# ProPrj_X-Link_V9_3_M_2024-11-03.net
KiCad netlist of a schematic drawn in EasyEDA Pro
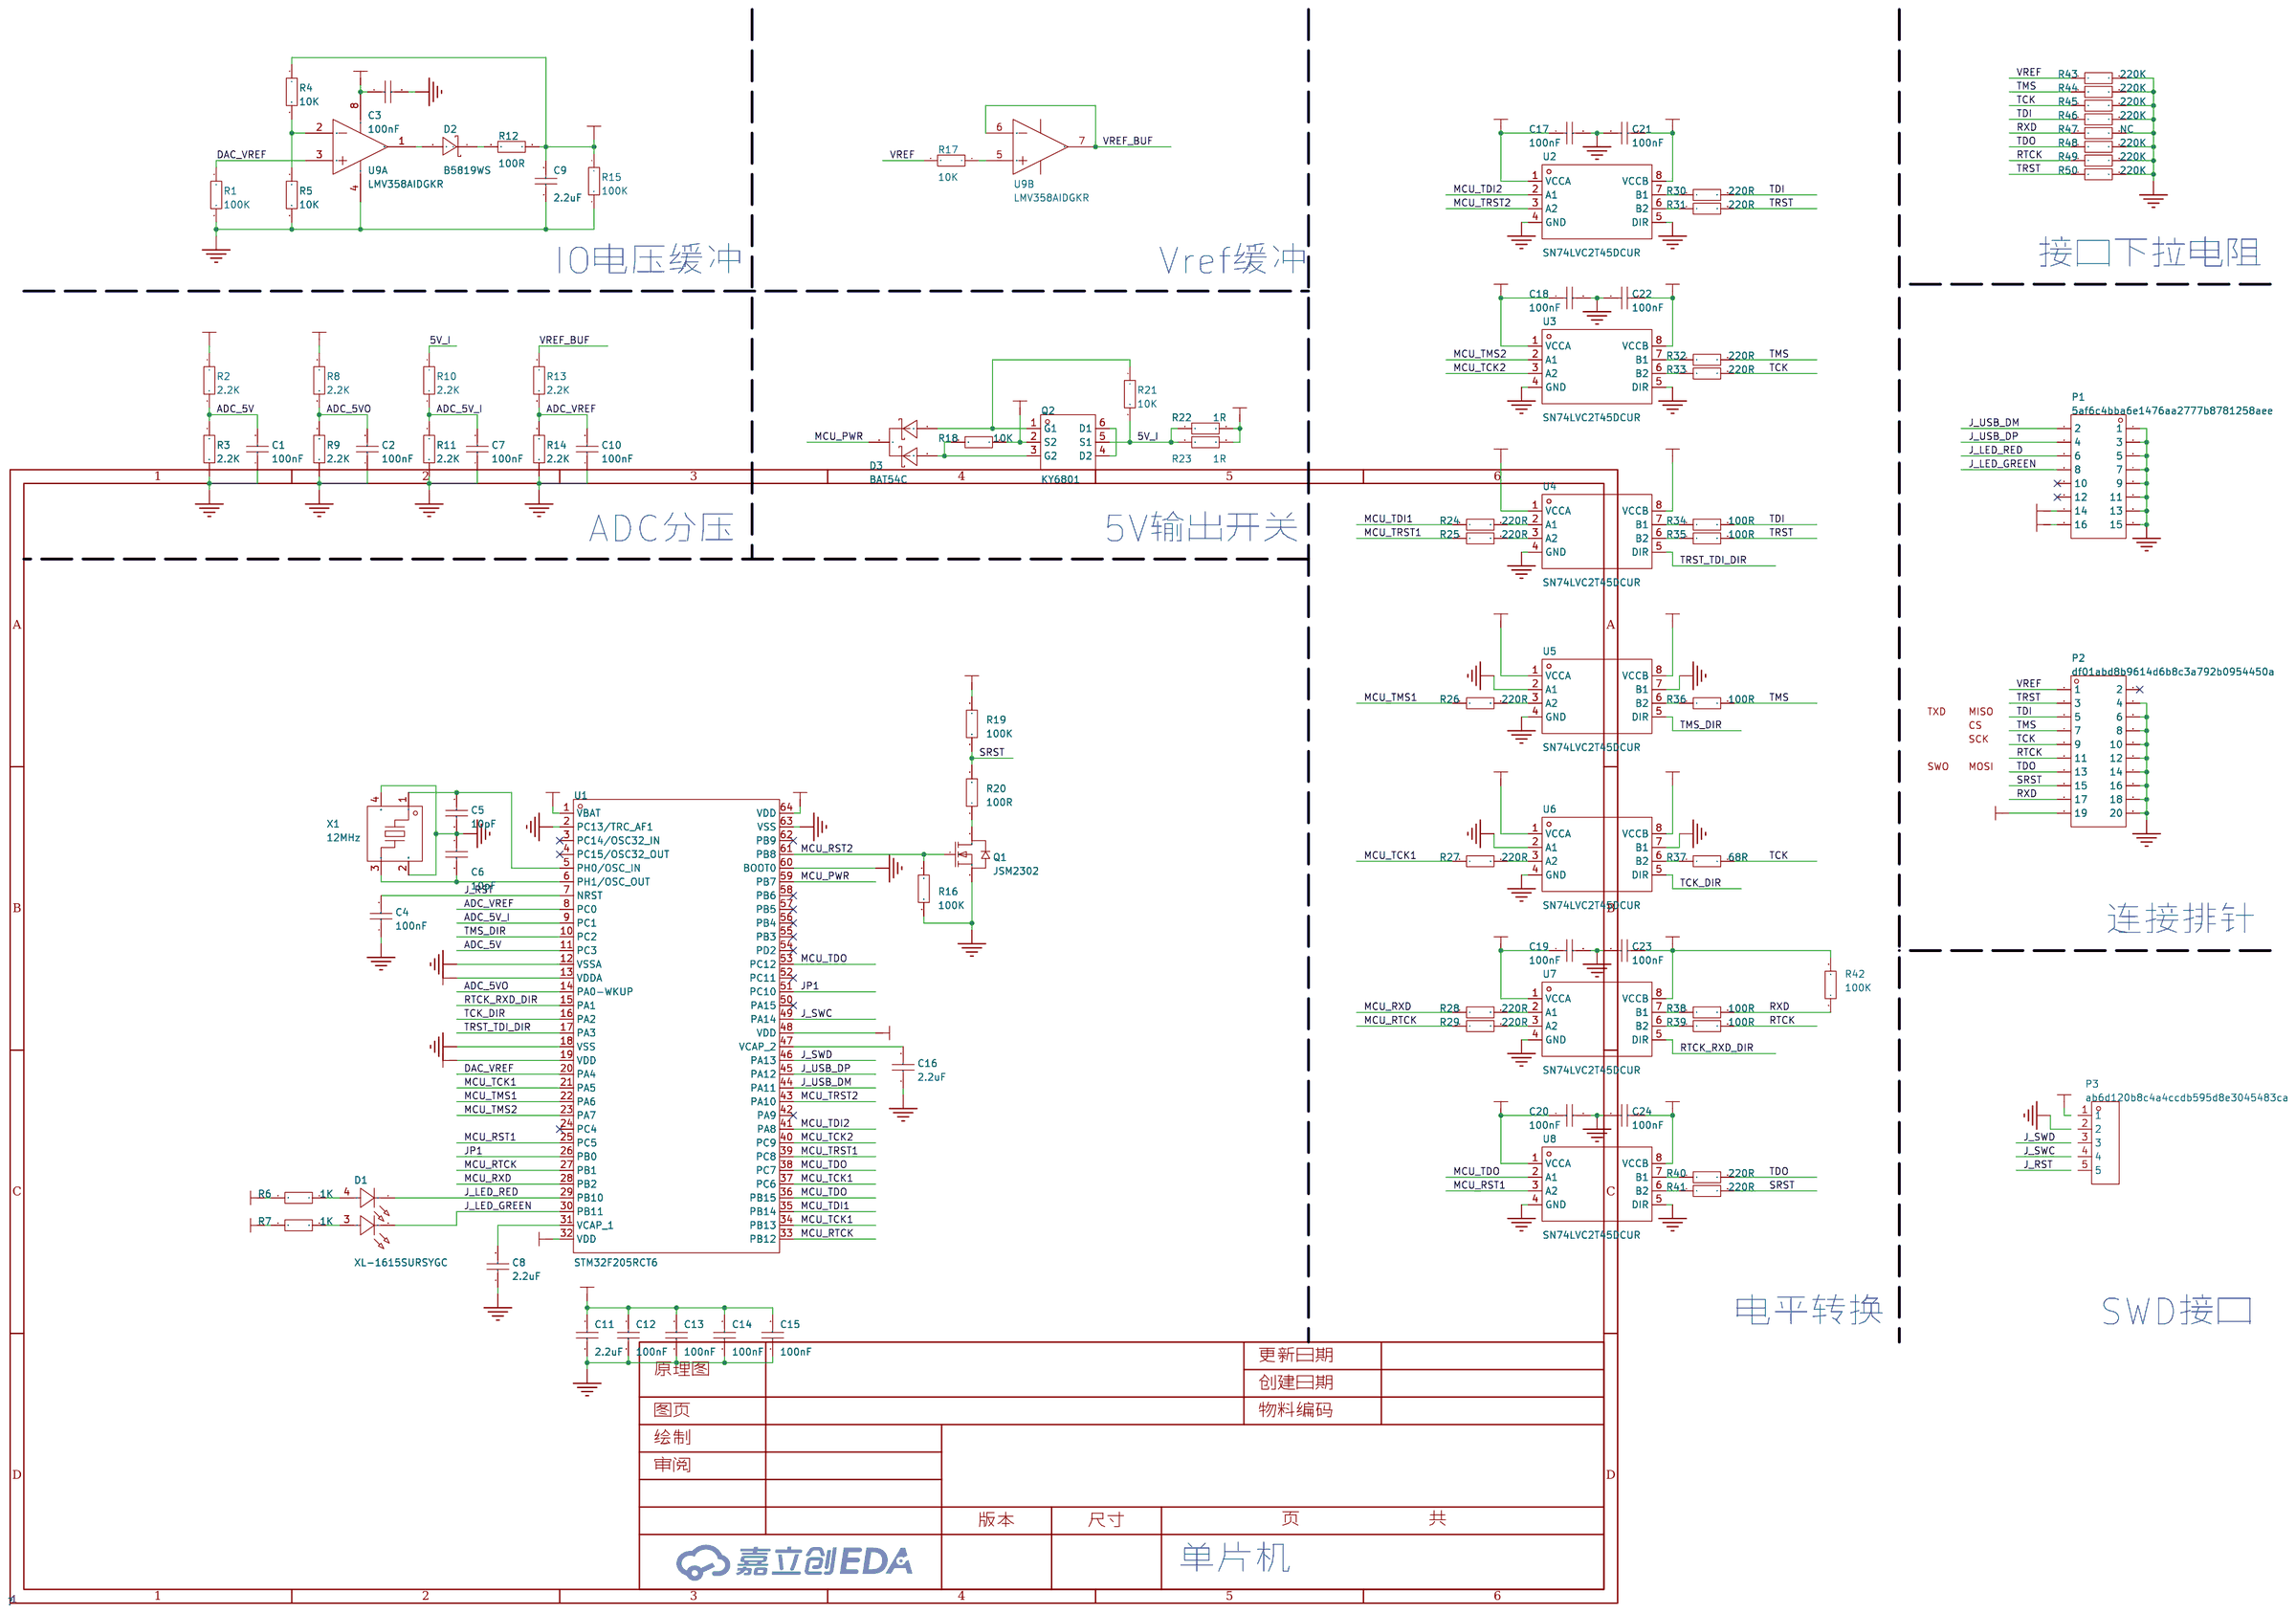
[diagram p0: schematic sheet]

(export (version "E")
  (design (tool "Eeschema 10.0.6"))
  (components
    (comp (ref "C1")
      (value "100nF")
      (footprint "easyedapro:C0402")
      (libsource (lib "easyedapro") (part "C0402"))
    )
    (comp (ref "C2")
      (value "100nF")
      (footprint "easyedapro:C0402")
      (libsource (lib "easyedapro") (part "C0402"))
    )
    (comp (ref "C3")
      (value "100nF")
      (footprint "easyedapro:C0402")
      (libsource (lib "easyedapro") (part "C0402"))
    )
    (comp (ref "C4")
      (value "100nF")
      (footprint "easyedapro:C0603")
      (libsource (lib "easyedapro") (part "C0603"))
    )
    (comp (ref "C5")
      (value "10pF")
      (footprint "easyedapro:C0402")
      (libsource (lib "easyedapro") (part "C0402"))
    )
    (comp (ref "C6")
      (value "10pF")
      (footprint "easyedapro:C0402")
      (libsource (lib "easyedapro") (part "C0402"))
    )
    (comp (ref "C7")
      (value "100nF")
      (footprint "easyedapro:C0402")
      (libsource (lib "easyedapro") (part "C0402"))
    )
    (comp (ref "C8")
      (value "2.2uF")
      (footprint "easyedapro:C0603")
      (libsource (lib "easyedapro") (part "C0603"))
    )
    (comp (ref "C9")
      (value "2.2uF")
      (footprint "easyedapro:C0402")
      (libsource (lib "easyedapro") (part "C0402"))
    )
    (comp (ref "C10")
      (value "100nF")
      (footprint "easyedapro:C0402")
      (libsource (lib "easyedapro") (part "C0402"))
    )
    (comp (ref "C11")
      (value "2.2uF")
      (footprint "easyedapro:C0603")
      (libsource (lib "easyedapro") (part "C0603"))
    )
    (comp (ref "C12")
      (value "100nF")
      (footprint "easyedapro:C0603")
      (libsource (lib "easyedapro") (part "C0603"))
    )
    (comp (ref "C13")
      (value "100nF")
      (footprint "easyedapro:C0603")
      (libsource (lib "easyedapro") (part "C0603"))
    )
    (comp (ref "C14")
      (value "100nF")
      (footprint "easyedapro:C0603")
      (libsource (lib "easyedapro") (part "C0603"))
    )
    (comp (ref "C15")
      (value "100nF")
      (footprint "easyedapro:C0603")
      (libsource (lib "easyedapro") (part "C0603"))
    )
    (comp (ref "C16")
      (value "2.2uF")
      (footprint "easyedapro:C0603")
      (libsource (lib "easyedapro") (part "C0603"))
    )
    (comp (ref "C17")
      (value "100nF")
      (footprint "easyedapro:C0603")
      (libsource (lib "easyedapro") (part "C0603"))
    )
    (comp (ref "C18")
      (value "100nF")
      (footprint "easyedapro:C0603")
      (libsource (lib "easyedapro") (part "C0603"))
    )
    (comp (ref "C19")
      (value "100nF")
      (footprint "easyedapro:C0603")
      (libsource (lib "easyedapro") (part "C0603"))
    )
    (comp (ref "C20")
      (value "100nF")
      (footprint "easyedapro:C0603")
      (libsource (lib "easyedapro") (part "C0603"))
    )
    (comp (ref "C21")
      (value "100nF")
      (footprint "easyedapro:C0603")
      (libsource (lib "easyedapro") (part "C0603"))
    )
    (comp (ref "C22")
      (value "100nF")
      (footprint "easyedapro:C0603")
      (libsource (lib "easyedapro") (part "C0603"))
    )
    (comp (ref "C23")
      (value "100nF")
      (footprint "easyedapro:C0603")
      (libsource (lib "easyedapro") (part "C0603"))
    )
    (comp (ref "C24")
      (value "100nF")
      (footprint "easyedapro:C0603")
      (libsource (lib "easyedapro") (part "C0603"))
    )
    (comp (ref "D1")
      (value "XL-1615SURSYGC")
      (footprint "easyedapro:LED1615")
      (fields (field (name "Manufacturer") "XINGLIGHT(成兴光)"))
      (libsource (lib "easyedapro") (part "LED1615"))
    )
    (comp (ref "D2")
      (value "B5819WS")
      (footprint "easyedapro:SOD-323_L1.8-W1.3-LS2.5-RD")
      (description "正向压降(Vf):600mV@1A;直流反向耐压(Vr):40V;平均整流电流(Io):1A;")
      (fields (field (name "Manufacturer") "CJ(江苏长电/长晶)"))
      (libsource (lib "easyedapro") (part "B5819WS_C22624"))
    )
    (comp (ref "D3")
      (value "BAT54C")
      (footprint "easyedapro:SOT-23-3_L2.9-W1.3-P1.90-LS2.4-BR")
      (description "二极管配置:1对共阴极;正向压降(Vf):1V@100mA;直流反向耐压(Vr):30V;平均整流电流(Io):100mA;")
      (fields (field (name "Manufacturer") "JSMSEMI(杰盛微)"))
      (libsource (lib "easyedapro") (part "BAR43CFILM"))
    )
    (comp (ref "P1")
      (value "5af6c4bba6e1476aa2777b8781258aee")
      (footprint "easyedapro:HDR-TH_16P-P1.27-V-M-R2-C8-S1.27-1")
      (libsource (lib "easyedapro") (part "HDR2x8_1.27"))
    )
    (comp (ref "P2")
      (value "df01abd8b9614d6b8c3a792b0954450a")
      (footprint "easyedapro:HDR-TH_20P-P1.27-V-M-R2-C10-S1.27")
      (libsource (lib "easyedapro") (part "HDR2x10_1.27"))
    )
    (comp (ref "P3")
      (value "ab6d120b8c4a4ccdb595d8e3045483ca")
      (footprint "easyedapro:HDR-TH_5P-P1.27-V-M")
      (libsource (lib "easyedapro") (part "HDR1x5_1.27"))
    )
    (comp (ref "Q1")
      (value "JSM2302")
      (footprint "easyedapro:SOT-23-3_L2.9-W1.3-P1.90-LS2.4-BR")
      (fields (field (name "Manufacturer") "JSMSEMI(杰盛微)"))
      (libsource (lib "easyedapro") (part "SI2302A"))
    )
    (comp (ref "Q2")
      (value "KY6801")
      (footprint "easyedapro:SOT-23-6_L2.9-W1.6-P0.95-LS2.8-BR")
      (description "类型:-;漏源电压(Vdss):-;连续漏极电流(Id):-;功率(Pd):-;导通电阻(RDS(on)@Vgs,Id):-;阈值电压(Vgs(th)@Id):-;")
      (fields (field (name "Manufacturer") "KY(韩景元)"))
      (libsource (lib "easyedapro") (part "FDC6312P_C241767"))
    )
    (comp (ref "R1")
      (value "100K")
      (footprint "easyedapro:R0402")
      (libsource (lib "easyedapro") (part "R0402"))
    )
    (comp (ref "R2")
      (value "2.2K")
      (footprint "easyedapro:R0402")
      (libsource (lib "easyedapro") (part "R0402"))
    )
    (comp (ref "R3")
      (value "2.2K")
      (footprint "easyedapro:R0402")
      (libsource (lib "easyedapro") (part "R0402"))
    )
    (comp (ref "R4")
      (value "10K")
      (footprint "easyedapro:R0402")
      (libsource (lib "easyedapro") (part "R0402"))
    )
    (comp (ref "R5")
      (value "10K")
      (footprint "easyedapro:R0402")
      (libsource (lib "easyedapro") (part "R0402"))
    )
    (comp (ref "R6") (value "1K") (footprint "easyedapro:R0603") (libsource (lib "easyedapro") (part "电阻")))
    (comp (ref "R7") (value "1K") (footprint "easyedapro:R0603") (libsource (lib "easyedapro") (part "电阻")))
    (comp (ref "R8")
      (value "2.2K")
      (footprint "easyedapro:R0402")
      (libsource (lib "easyedapro") (part "R0402"))
    )
    (comp (ref "R9")
      (value "2.2K")
      (footprint "easyedapro:R0402")
      (libsource (lib "easyedapro") (part "R0402"))
    )
    (comp (ref "R10")
      (value "2.2K")
      (footprint "easyedapro:R0402")
      (libsource (lib "easyedapro") (part "R0402"))
    )
    (comp (ref "R11")
      (value "2.2K")
      (footprint "easyedapro:R0402")
      (libsource (lib "easyedapro") (part "R0402"))
    )
    (comp (ref "R12")
      (value "100R")
      (footprint "easyedapro:R0402")
      (libsource (lib "easyedapro") (part "R0402"))
    )
    (comp (ref "R13")
      (value "2.2K")
      (footprint "easyedapro:R0402")
      (libsource (lib "easyedapro") (part "R0402"))
    )
    (comp (ref "R14")
      (value "2.2K")
      (footprint "easyedapro:R0402")
      (libsource (lib "easyedapro") (part "R0402"))
    )
    (comp (ref "R15")
      (value "100K")
      (footprint "easyedapro:R0402")
      (libsource (lib "easyedapro") (part "R0402"))
    )
    (comp (ref "R16")
      (value "100K")
      (footprint "easyedapro:R0603")
      (libsource (lib "easyedapro") (part "电阻"))
    )
    (comp (ref "R17")
      (value "10K")
      (footprint "easyedapro:R0402")
      (libsource (lib "easyedapro") (part "R0402"))
    )
    (comp (ref "R18") (value "10K") (footprint "easyedapro:R0603") (libsource (lib "easyedapro") (part "电阻")))
    (comp (ref "R19")
      (value "100K")
      (footprint "easyedapro:R0603")
      (libsource (lib "easyedapro") (part "电阻"))
    )
    (comp (ref "R20")
      (value "100R")
      (footprint "easyedapro:R0603")
      (libsource (lib "easyedapro") (part "电阻"))
    )
    (comp (ref "R21") (value "10K") (footprint "easyedapro:R0603") (libsource (lib "easyedapro") (part "电阻")))
    (comp (ref "R22")
      (value "1R")
      (footprint "easyedapro:R0805")
      (libsource (lib "easyedapro") (part "R0805"))
    )
    (comp (ref "R23")
      (value "1R")
      (footprint "easyedapro:R0805")
      (libsource (lib "easyedapro") (part "R0805"))
    )
    (comp (ref "R24")
      (value "220R")
      (footprint "easyedapro:R0603")
      (libsource (lib "easyedapro") (part "电阻"))
    )
    (comp (ref "R25")
      (value "220R")
      (footprint "easyedapro:R0603")
      (libsource (lib "easyedapro") (part "电阻"))
    )
    (comp (ref "R26")
      (value "220R")
      (footprint "easyedapro:R0603")
      (libsource (lib "easyedapro") (part "电阻"))
    )
    (comp (ref "R27")
      (value "220R")
      (footprint "easyedapro:R0603")
      (libsource (lib "easyedapro") (part "电阻"))
    )
    (comp (ref "R28")
      (value "220R")
      (footprint "easyedapro:R0603")
      (libsource (lib "easyedapro") (part "电阻"))
    )
    (comp (ref "R29")
      (value "220R")
      (footprint "easyedapro:R0603")
      (libsource (lib "easyedapro") (part "电阻"))
    )
    (comp (ref "R30")
      (value "220R")
      (footprint "easyedapro:R0603")
      (libsource (lib "easyedapro") (part "电阻"))
    )
    (comp (ref "R31")
      (value "220R")
      (footprint "easyedapro:R0603")
      (libsource (lib "easyedapro") (part "电阻"))
    )
    (comp (ref "R32")
      (value "220R")
      (footprint "easyedapro:R0603")
      (libsource (lib "easyedapro") (part "电阻"))
    )
    (comp (ref "R33")
      (value "220R")
      (footprint "easyedapro:R0603")
      (libsource (lib "easyedapro") (part "电阻"))
    )
    (comp (ref "R34")
      (value "100R")
      (footprint "easyedapro:R0603")
      (libsource (lib "easyedapro") (part "电阻"))
    )
    (comp (ref "R35")
      (value "100R")
      (footprint "easyedapro:R0603")
      (libsource (lib "easyedapro") (part "电阻"))
    )
    (comp (ref "R36")
      (value "100R")
      (footprint "easyedapro:R0603")
      (libsource (lib "easyedapro") (part "电阻"))
    )
    (comp (ref "R37") (value "68R") (footprint "easyedapro:R0603") (libsource (lib "easyedapro") (part "电阻")))
    (comp (ref "R38")
      (value "100R")
      (footprint "easyedapro:R0603")
      (libsource (lib "easyedapro") (part "电阻"))
    )
    (comp (ref "R39")
      (value "100R")
      (footprint "easyedapro:R0603")
      (libsource (lib "easyedapro") (part "电阻"))
    )
    (comp (ref "R40")
      (value "220R")
      (footprint "easyedapro:R0603")
      (libsource (lib "easyedapro") (part "电阻"))
    )
    (comp (ref "R41")
      (value "220R")
      (footprint "easyedapro:R0603")
      (libsource (lib "easyedapro") (part "电阻"))
    )
    (comp (ref "R42")
      (value "100K")
      (footprint "easyedapro:R0603")
      (libsource (lib "easyedapro") (part "电阻"))
    )
    (comp (ref "R43")
      (value "220K")
      (footprint "easyedapro:R0603")
      (libsource (lib "easyedapro") (part "电阻"))
    )
    (comp (ref "R44")
      (value "220K")
      (footprint "easyedapro:R0603")
      (libsource (lib "easyedapro") (part "电阻"))
    )
    (comp (ref "R45")
      (value "220K")
      (footprint "easyedapro:R0603")
      (libsource (lib "easyedapro") (part "电阻"))
    )
    (comp (ref "R46")
      (value "220K")
      (footprint "easyedapro:R0603")
      (libsource (lib "easyedapro") (part "电阻"))
    )
    (comp (ref "R47") (value "NC") (footprint "easyedapro:R0603") (libsource (lib "easyedapro") (part "电阻")))
    (comp (ref "R48")
      (value "220K")
      (footprint "easyedapro:R0603")
      (libsource (lib "easyedapro") (part "电阻"))
    )
    (comp (ref "R49")
      (value "220K")
      (footprint "easyedapro:R0603")
      (libsource (lib "easyedapro") (part "电阻"))
    )
    (comp (ref "R50")
      (value "220K")
      (footprint "easyedapro:R0603")
      (libsource (lib "easyedapro") (part "电阻"))
    )
    (comp (ref "U1")
      (value "STM32F205RCT6")
      (footprint "easyedapro:LQFP-64_L10.0-W10.0-P0.50-LS12.0-BL")
      (description "CPU内核:CM3;程序存储容量:256KB;GPIO端口数量:51;工作电压范围:1.8V~3.6V;CPU最大主频:120MHz;")
      (fields (field (name "Manufacturer") "ST(意法半导体)"))
      (libsource (lib "easyedapro") (part "STM32F205RCT6"))
    )
    (comp (ref "U2")
      (value "SN74LVC2T45DCUR")
      (footprint "easyedapro:VSSOP-8_L2.4-W2.1-P0.50-LS3.2-BR")
      (description "SN74LVC2T45 具有可配置电压转换和三态输出的 2 位双电源总线收发器")
      (fields (field (name "Manufacturer") "TI(德州仪器)"))
      (libsource (lib "easyedapro") (part "SN74LVC2T45DCUR"))
    )
    (comp (ref "U3")
      (value "SN74LVC2T45DCUR")
      (footprint "easyedapro:VSSOP-8_L2.4-W2.1-P0.50-LS3.2-BR")
      (description "SN74LVC2T45 具有可配置电压转换和三态输出的 2 位双电源总线收发器")
      (fields (field (name "Manufacturer") "TI(德州仪器)"))
      (libsource (lib "easyedapro") (part "SN74LVC2T45DCUR"))
    )
    (comp (ref "U4")
      (value "SN74LVC2T45DCUR")
      (footprint "easyedapro:VSSOP-8_L2.4-W2.1-P0.50-LS3.2-BR")
      (description "SN74LVC2T45 具有可配置电压转换和三态输出的 2 位双电源总线收发器")
      (fields (field (name "Manufacturer") "TI(德州仪器)"))
      (libsource (lib "easyedapro") (part "SN74LVC2T45DCUR"))
    )
    (comp (ref "U5")
      (value "SN74LVC2T45DCUR")
      (footprint "easyedapro:VSSOP-8_L2.4-W2.1-P0.50-LS3.2-BR")
      (description "SN74LVC2T45 具有可配置电压转换和三态输出的 2 位双电源总线收发器")
      (fields (field (name "Manufacturer") "TI(德州仪器)"))
      (libsource (lib "easyedapro") (part "SN74LVC2T45DCUR"))
    )
    (comp (ref "U6")
      (value "SN74LVC2T45DCUR")
      (footprint "easyedapro:VSSOP-8_L2.4-W2.1-P0.50-LS3.2-BR")
      (description "SN74LVC2T45 具有可配置电压转换和三态输出的 2 位双电源总线收发器")
      (fields (field (name "Manufacturer") "TI(德州仪器)"))
      (libsource (lib "easyedapro") (part "SN74LVC2T45DCUR"))
    )
    (comp (ref "U7")
      (value "SN74LVC2T45DCUR")
      (footprint "easyedapro:VSSOP-8_L2.4-W2.1-P0.50-LS3.2-BR")
      (description "SN74LVC2T45 具有可配置电压转换和三态输出的 2 位双电源总线收发器")
      (fields (field (name "Manufacturer") "TI(德州仪器)"))
      (libsource (lib "easyedapro") (part "SN74LVC2T45DCUR"))
    )
    (comp (ref "U8")
      (value "SN74LVC2T45DCUR")
      (footprint "easyedapro:VSSOP-8_L2.4-W2.1-P0.50-LS3.2-BR")
      (description "SN74LVC2T45 具有可配置电压转换和三态输出的 2 位双电源总线收发器")
      (fields (field (name "Manufacturer") "TI(德州仪器)"))
      (libsource (lib "easyedapro") (part "SN74LVC2T45DCUR"))
    )
    (comp (ref "U9")
      (value "LMV358AIDGKR")
      (footprint "easyedapro:VSSOP-8_L3.0-W3.0-P0.65-LS5.0-BL")
      (description "放大器数:双路;增益带宽积(GBP):1MHz;输入偏置电流(Ib):10pA;压摆率(SR):1.7V/us;带宽(-3db):-;轨到轨:-;")
      (fields (field (name "Manufacturer") "TI(德州仪器)"))
      (libsource (lib "easyedapro") (part "LMV358AIDGKR"))
    )
    (comp (ref "X1")
      (value "12MHz")
      (footprint "easyedapro:CRYSTAL-SMD_4P-L3.2-W2.5-BL-A")
      (libsource (lib "easyedapro") (part "XTAL3225"))
    )
  )
  (nets
    (net (code "1") (name "/5V_I") (class "Default")
      (node (ref "Q2") (pin "5") (pinfunction "S1_5") (pintype "unspecified"))
      (node (ref "R10") (pin "1") (pinfunction "1_1") (pintype "input"))
      (node (ref "R21") (pin "2") (pinfunction "2_2") (pintype "input"))
      (node (ref "R22") (pin "1") (pinfunction "1_1") (pintype "input"))
      (node (ref "R23") (pin "1") (pinfunction "1_1") (pintype "input"))
    )
    (net (code "2") (name "/ADC_5V") (class "Default")
      (node (ref "C1") (pin "2") (pinfunction "2_2") (pintype "input"))
      (node (ref "R2") (pin "2") (pinfunction "2_2") (pintype "input"))
      (node (ref "R3") (pin "1") (pinfunction "1_1") (pintype "input"))
      (node (ref "U1") (pin "11") (pinfunction "PC3_11") (pintype "unspecified"))
    )
    (net (code "3") (name "/ADC_5VO") (class "Default")
      (node (ref "C2") (pin "2") (pinfunction "2_2") (pintype "input"))
      (node (ref "R8") (pin "2") (pinfunction "2_2") (pintype "input"))
      (node (ref "R9") (pin "1") (pinfunction "1_1") (pintype "input"))
      (node (ref "U1") (pin "14") (pinfunction "PA0-WKUP_14") (pintype "unspecified"))
    )
    (net (code "4") (name "/ADC_5V_I") (class "Default")
      (node (ref "C7") (pin "2") (pinfunction "2_2") (pintype "input"))
      (node (ref "R10") (pin "2") (pinfunction "2_2") (pintype "input"))
      (node (ref "R11") (pin "1") (pinfunction "1_1") (pintype "input"))
      (node (ref "U1") (pin "9") (pinfunction "PC1_9") (pintype "unspecified"))
    )
    (net (code "5") (name "/ADC_VREF") (class "Default")
      (node (ref "C10") (pin "2") (pinfunction "2_2") (pintype "input"))
      (node (ref "R13") (pin "2") (pinfunction "2_2") (pintype "input"))
      (node (ref "R14") (pin "1") (pinfunction "1_1") (pintype "input"))
      (node (ref "U1") (pin "8") (pinfunction "PC0_8") (pintype "unspecified"))
    )
    (net (code "6") (name "/DAC_VREF") (class "Default")
      (node (ref "R1") (pin "1") (pinfunction "1_1") (pintype "input"))
      (node (ref "U1") (pin "20") (pinfunction "PA4_20") (pintype "unspecified"))
      (node (ref "U9") (pin "3") (pinfunction "+INA_3") (pintype "unspecified"))
    )
    (net (code "7") (name "/JP1") (class "Default")
      (node (ref "U1") (pin "26") (pinfunction "PB0_26") (pintype "unspecified"))
      (node (ref "U1") (pin "51") (pinfunction "PC10_51") (pintype "unspecified"))
    )
    (net (code "8") (name "/J_LED_GREEN") (class "Default")
      (node (ref "D1") (pin "2") (pinfunction "K_2") (pintype "unspecified"))
      (node (ref "P1") (pin "8") (pinfunction "8_8") (pintype "unspecified"))
      (node (ref "U1") (pin "30") (pinfunction "PB11_30") (pintype "unspecified"))
    )
    (net (code "9") (name "/J_LED_RED") (class "Default")
      (node (ref "D1") (pin "1") (pinfunction "K_1") (pintype "unspecified"))
      (node (ref "P1") (pin "6") (pinfunction "6_6") (pintype "unspecified"))
      (node (ref "U1") (pin "29") (pinfunction "PB10_29") (pintype "unspecified"))
    )
    (net (code "10") (name "/J_RST") (class "Default")
      (node (ref "C4") (pin "2") (pinfunction "2_2") (pintype "input"))
      (node (ref "U1") (pin "7") (pinfunction "NRST_7") (pintype "unspecified"))
    )
    (net (code "11") (name "/J_SWC") (class "Default")
      (node (ref "U1") (pin "49") (pinfunction "PA14_49") (pintype "unspecified"))
    )
    (net (code "12") (name "/J_SWD") (class "Default")
      (node (ref "U1") (pin "46") (pinfunction "PA13_46") (pintype "unspecified"))
    )
    (net (code "13") (name "/J_USB_DM") (class "Default")
      (node (ref "P1") (pin "2") (pinfunction "2_2") (pintype "unspecified"))
      (node (ref "U1") (pin "44") (pinfunction "PA11_44") (pintype "unspecified"))
    )
    (net (code "14") (name "/J_USB_DP") (class "Default")
      (node (ref "P1") (pin "4") (pinfunction "4_4") (pintype "unspecified"))
      (node (ref "U1") (pin "45") (pinfunction "PA12_45") (pintype "unspecified"))
    )
    (net (code "15") (name "/MCU_PWR") (class "Default")
      (node (ref "D3") (pin "3") (pinfunction "K_3") (pintype "unspecified"))
      (node (ref "U1") (pin "59") (pinfunction "PB7_59") (pintype "unspecified"))
    )
    (net (code "16") (name "/MCU_RST1") (class "Default")
      (node (ref "U1") (pin "25") (pinfunction "PC5_25") (pintype "unspecified"))
      (node (ref "U8") (pin "3") (pinfunction "A2_3") (pintype "unspecified"))
    )
    (net (code "17") (name "/MCU_RST2") (class "Default")
      (node (ref "Q1") (pin "1") (pinfunction "G_1") (pintype "unspecified"))
      (node (ref "R16") (pin "1") (pinfunction "1_1") (pintype "input"))
      (node (ref "U1") (pin "61") (pinfunction "PB8_61") (pintype "unspecified"))
    )
    (net (code "18") (name "/MCU_RTCK") (class "Default")
      (node (ref "R29") (pin "1") (pinfunction "1_1") (pintype "input"))
      (node (ref "U1") (pin "27") (pinfunction "PB1_27") (pintype "unspecified"))
      (node (ref "U1") (pin "33") (pinfunction "PB12_33") (pintype "unspecified"))
    )
    (net (code "19") (name "/MCU_RXD") (class "Default")
      (node (ref "R28") (pin "1") (pinfunction "1_1") (pintype "input"))
      (node (ref "U1") (pin "28") (pinfunction "PB2_28") (pintype "unspecified"))
    )
    (net (code "20") (name "/MCU_TCK1") (class "Default")
      (node (ref "R27") (pin "1") (pinfunction "1_1") (pintype "input"))
      (node (ref "U1") (pin "21") (pinfunction "PA5_21") (pintype "unspecified"))
      (node (ref "U1") (pin "34") (pinfunction "PB13_34") (pintype "unspecified"))
      (node (ref "U1") (pin "37") (pinfunction "PC6_37") (pintype "unspecified"))
    )
    (net (code "21") (name "/MCU_TCK2") (class "Default")
      (node (ref "U1") (pin "40") (pinfunction "PC9_40") (pintype "unspecified"))
      (node (ref "U3") (pin "3") (pinfunction "A2_3") (pintype "unspecified"))
    )
    (net (code "22") (name "/MCU_TDI1") (class "Default")
      (node (ref "R24") (pin "1") (pinfunction "1_1") (pintype "input"))
      (node (ref "U1") (pin "35") (pinfunction "PB14_35") (pintype "unspecified"))
    )
    (net (code "23") (name "/MCU_TDI2") (class "Default")
      (node (ref "U1") (pin "41") (pinfunction "PA8_41") (pintype "unspecified"))
      (node (ref "U2") (pin "2") (pinfunction "A1_2") (pintype "unspecified"))
    )
    (net (code "24") (name "/MCU_TDO") (class "Default")
      (node (ref "U1") (pin "36") (pinfunction "PB15_36") (pintype "unspecified"))
      (node (ref "U1") (pin "38") (pinfunction "PC7_38") (pintype "unspecified"))
      (node (ref "U1") (pin "53") (pinfunction "PC12_53") (pintype "unspecified"))
      (node (ref "U8") (pin "2") (pinfunction "A1_2") (pintype "unspecified"))
    )
    (net (code "25") (name "/MCU_TMS1") (class "Default")
      (node (ref "R26") (pin "1") (pinfunction "1_1") (pintype "input"))
      (node (ref "U1") (pin "22") (pinfunction "PA6_22") (pintype "unspecified"))
    )
    (net (code "26") (name "/MCU_TMS2") (class "Default")
      (node (ref "U1") (pin "23") (pinfunction "PA7_23") (pintype "unspecified"))
      (node (ref "U3") (pin "2") (pinfunction "A1_2") (pintype "unspecified"))
    )
    (net (code "27") (name "/MCU_TRST1") (class "Default")
      (node (ref "R25") (pin "1") (pinfunction "1_1") (pintype "input"))
      (node (ref "U1") (pin "39") (pinfunction "PC8_39") (pintype "unspecified"))
    )
    (net (code "28") (name "/MCU_TRST2") (class "Default")
      (node (ref "U1") (pin "43") (pinfunction "PA10_43") (pintype "unspecified"))
      (node (ref "U2") (pin "3") (pinfunction "A2_3") (pintype "unspecified"))
    )
    (net (code "29") (name "/RTCK") (class "Default")
      (node (ref "P2") (pin "11") (pinfunction "11_11") (pintype "unspecified"))
      (node (ref "R39") (pin "2") (pinfunction "2_2") (pintype "input"))
      (node (ref "R49") (pin "1") (pinfunction "1_1") (pintype "input"))
    )
    (net (code "30") (name "/RTCK_RXD_DIR") (class "Default")
      (node (ref "U1") (pin "15") (pinfunction "PA1_15") (pintype "unspecified"))
      (node (ref "U7") (pin "5") (pinfunction "DIR_5") (pintype "unspecified"))
    )
    (net (code "31") (name "/RXD") (class "Default")
      (node (ref "P2") (pin "17") (pinfunction "17_17") (pintype "unspecified"))
      (node (ref "R38") (pin "2") (pinfunction "2_2") (pintype "input"))
      (node (ref "R42") (pin "1") (pinfunction "1_1") (pintype "input"))
      (node (ref "R47") (pin "1") (pinfunction "1_1") (pintype "input"))
    )
    (net (code "32") (name "/SRST") (class "Default")
      (node (ref "P2") (pin "15") (pinfunction "15_15") (pintype "unspecified"))
      (node (ref "R19") (pin "2") (pinfunction "2_2") (pintype "input"))
      (node (ref "R20") (pin "2") (pinfunction "2_2") (pintype "input"))
      (node (ref "R41") (pin "2") (pinfunction "2_2") (pintype "input"))
    )
    (net (code "33") (name "/TCK") (class "Default")
      (node (ref "P2") (pin "9") (pinfunction "9_9") (pintype "unspecified"))
      (node (ref "R33") (pin "2") (pinfunction "2_2") (pintype "input"))
      (node (ref "R37") (pin "2") (pinfunction "2_2") (pintype "input"))
      (node (ref "R45") (pin "1") (pinfunction "1_1") (pintype "input"))
    )
    (net (code "34") (name "/TCK_DIR") (class "Default")
      (node (ref "U1") (pin "16") (pinfunction "PA2_16") (pintype "unspecified"))
      (node (ref "U6") (pin "5") (pinfunction "DIR_5") (pintype "unspecified"))
    )
    (net (code "35") (name "/TDI") (class "Default")
      (node (ref "P2") (pin "5") (pinfunction "5_5") (pintype "unspecified"))
      (node (ref "R30") (pin "2") (pinfunction "2_2") (pintype "input"))
      (node (ref "R34") (pin "2") (pinfunction "2_2") (pintype "input"))
      (node (ref "R46") (pin "1") (pinfunction "1_1") (pintype "input"))
    )
    (net (code "36") (name "/TDO") (class "Default")
      (node (ref "P2") (pin "13") (pinfunction "13_13") (pintype "unspecified"))
      (node (ref "R40") (pin "2") (pinfunction "2_2") (pintype "input"))
      (node (ref "R48") (pin "1") (pinfunction "1_1") (pintype "input"))
    )
    (net (code "37") (name "/TMS") (class "Default")
      (node (ref "P2") (pin "7") (pinfunction "7_7") (pintype "unspecified"))
      (node (ref "R32") (pin "2") (pinfunction "2_2") (pintype "input"))
      (node (ref "R36") (pin "2") (pinfunction "2_2") (pintype "input"))
      (node (ref "R44") (pin "1") (pinfunction "1_1") (pintype "input"))
    )
    (net (code "38") (name "/TMS_DIR") (class "Default")
      (node (ref "U1") (pin "10") (pinfunction "PC2_10") (pintype "unspecified"))
      (node (ref "U5") (pin "5") (pinfunction "DIR_5") (pintype "unspecified"))
    )
    (net (code "39") (name "/TRST") (class "Default")
      (node (ref "P2") (pin "3") (pinfunction "3_3") (pintype "unspecified"))
      (node (ref "R31") (pin "2") (pinfunction "2_2") (pintype "input"))
      (node (ref "R35") (pin "2") (pinfunction "2_2") (pintype "input"))
      (node (ref "R50") (pin "1") (pinfunction "1_1") (pintype "input"))
    )
    (net (code "40") (name "/TRST_TDI_DIR") (class "Default")
      (node (ref "U1") (pin "17") (pinfunction "PA3_17") (pintype "unspecified"))
      (node (ref "U4") (pin "5") (pinfunction "DIR_5") (pintype "unspecified"))
    )
    (net (code "41") (name "/VREF") (class "Default")
      (node (ref "P2") (pin "1") (pinfunction "1_1") (pintype "unspecified"))
      (node (ref "R17") (pin "2") (pinfunction "2_2") (pintype "input"))
      (node (ref "R43") (pin "1") (pinfunction "1_1") (pintype "input"))
    )
    (net (code "42") (name "/VREF_BUF") (class "Default")
      (node (ref "R13") (pin "1") (pinfunction "1_1") (pintype "input"))
      (node (ref "U9") (pin "6") (pinfunction "-INB_6") (pintype "unspecified"))
      (node (ref "U9") (pin "7") (pinfunction "OUTB_7") (pintype "output"))
    )
    (net (code "43") (name "3.3V") (class "Default")
      (node (ref "C11") (pin "2") (pinfunction "2_2") (pintype "input"))
      (node (ref "C12") (pin "2") (pinfunction "2_2") (pintype "input"))
      (node (ref "C13") (pin "2") (pinfunction "2_2") (pintype "input"))
      (node (ref "C14") (pin "2") (pinfunction "2_2") (pintype "input"))
      (node (ref "C15") (pin "2") (pinfunction "2_2") (pintype "input"))
      (node (ref "C17") (pin "1") (pinfunction "1_1") (pintype "input"))
      (node (ref "C18") (pin "1") (pinfunction "1_1") (pintype "input"))
      (node (ref "C19") (pin "1") (pinfunction "1_1") (pintype "input"))
      (node (ref "C20") (pin "1") (pinfunction "1_1") (pintype "input"))
      (node (ref "P1") (pin "14") (pinfunction "14_14") (pintype "unspecified"))
      (node (ref "R6") (pin "2") (pinfunction "2_2") (pintype "input"))
      (node (ref "R7") (pin "2") (pinfunction "2_2") (pintype "input"))
      (node (ref "U1") (pin "1") (pinfunction "VBAT_1") (pintype "unspecified"))
      (node (ref "U1") (pin "13") (pinfunction "VDDA_13") (pintype "unspecified"))
      (node (ref "U1") (pin "19") (pinfunction "VDD_19") (pintype "unspecified"))
      (node (ref "U1") (pin "32") (pinfunction "VDD_32") (pintype "unspecified"))
      (node (ref "U1") (pin "48") (pinfunction "VDD_48") (pintype "unspecified"))
      (node (ref "U1") (pin "64") (pinfunction "VDD_64") (pintype "unspecified"))
      (node (ref "U2") (pin "1") (pinfunction "VCCA_1") (pintype "unspecified"))
      (node (ref "U3") (pin "1") (pinfunction "VCCA_1") (pintype "unspecified"))
      (node (ref "U4") (pin "1") (pinfunction "VCCA_1") (pintype "unspecified"))
      (node (ref "U5") (pin "1") (pinfunction "VCCA_1") (pintype "unspecified"))
      (node (ref "U6") (pin "1") (pinfunction "VCCA_1") (pintype "unspecified"))
      (node (ref "U7") (pin "1") (pinfunction "VCCA_1") (pintype "unspecified"))
      (node (ref "U8") (pin "1") (pinfunction "VCCA_1") (pintype "unspecified"))
    )
    (net (code "44") (name "5V") (class "Default")
      (node (ref "C3") (pin "1") (pinfunction "1_1") (pintype "input"))
      (node (ref "P1") (pin "16") (pinfunction "16_16") (pintype "unspecified"))
      (node (ref "R2") (pin "1") (pinfunction "1_1") (pintype "input"))
      (node (ref "R22") (pin "2") (pinfunction "2_2") (pintype "input"))
      (node (ref "R23") (pin "2") (pinfunction "2_2") (pintype "input"))
      (node (ref "U9") (pin "8") (pinfunction "V+_8") (pintype "unspecified"))
    )
    (net (code "45") (name "5V_OUT") (class "Default")
      (node (ref "P2") (pin "19") (pinfunction "19_19") (pintype "unspecified"))
      (node (ref "Q2") (pin "2") (pinfunction "S2_2") (pintype "unspecified"))
      (node (ref "R18") (pin "1") (pinfunction "1_1") (pintype "input"))
      (node (ref "R8") (pin "1") (pinfunction "1_1") (pintype "input"))
    )
    (net (code "46") (name "GND") (class "Default")
      (node (ref "C1") (pin "1") (pinfunction "1_1") (pintype "input"))
      (node (ref "C10") (pin "1") (pinfunction "1_1") (pintype "input"))
      (node (ref "C11") (pin "1") (pinfunction "1_1") (pintype "input"))
      (node (ref "C12") (pin "1") (pinfunction "1_1") (pintype "input"))
      (node (ref "C13") (pin "1") (pinfunction "1_1") (pintype "input"))
      (node (ref "C14") (pin "1") (pinfunction "1_1") (pintype "input"))
      (node (ref "C15") (pin "1") (pinfunction "1_1") (pintype "input"))
      (node (ref "C16") (pin "1") (pinfunction "1_1") (pintype "input"))
      (node (ref "C17") (pin "2") (pinfunction "2_2") (pintype "input"))
      (node (ref "C18") (pin "2") (pinfunction "2_2") (pintype "input"))
      (node (ref "C19") (pin "2") (pinfunction "2_2") (pintype "input"))
      (node (ref "C2") (pin "1") (pinfunction "1_1") (pintype "input"))
      (node (ref "C20") (pin "2") (pinfunction "2_2") (pintype "input"))
      (node (ref "C21") (pin "1") (pinfunction "1_1") (pintype "input"))
      (node (ref "C22") (pin "1") (pinfunction "1_1") (pintype "input"))
      (node (ref "C23") (pin "1") (pinfunction "1_1") (pintype "input"))
      (node (ref "C24") (pin "1") (pinfunction "1_1") (pintype "input"))
      (node (ref "C3") (pin "2") (pinfunction "2_2") (pintype "input"))
      (node (ref "C4") (pin "1") (pinfunction "1_1") (pintype "input"))
      (node (ref "C5") (pin "2") (pinfunction "2_2") (pintype "input"))
      (node (ref "C6") (pin "1") (pinfunction "1_1") (pintype "input"))
      (node (ref "C7") (pin "1") (pinfunction "1_1") (pintype "input"))
      (node (ref "C8") (pin "1") (pinfunction "1_1") (pintype "input"))
      (node (ref "C9") (pin "1") (pinfunction "1_1") (pintype "input"))
      (node (ref "P1") (pin "1") (pinfunction "1_1") (pintype "unspecified"))
      (node (ref "P1") (pin "11") (pinfunction "11_11") (pintype "unspecified"))
      (node (ref "P1") (pin "13") (pinfunction "13_13") (pintype "unspecified"))
      (node (ref "P1") (pin "15") (pinfunction "15_15") (pintype "unspecified"))
      (node (ref "P1") (pin "3") (pinfunction "3_3") (pintype "unspecified"))
      (node (ref "P1") (pin "5") (pinfunction "5_5") (pintype "unspecified"))
      (node (ref "P1") (pin "7") (pinfunction "7_7") (pintype "unspecified"))
      (node (ref "P1") (pin "9") (pinfunction "9_9") (pintype "unspecified"))
      (node (ref "P2") (pin "10") (pinfunction "10_10") (pintype "unspecified"))
      (node (ref "P2") (pin "12") (pinfunction "12_12") (pintype "unspecified"))
      (node (ref "P2") (pin "14") (pinfunction "14_14") (pintype "unspecified"))
      (node (ref "P2") (pin "16") (pinfunction "16_16") (pintype "unspecified"))
      (node (ref "P2") (pin "18") (pinfunction "18_18") (pintype "unspecified"))
      (node (ref "P2") (pin "20") (pinfunction "20_20") (pintype "unspecified"))
      (node (ref "P2") (pin "4") (pinfunction "4_4") (pintype "unspecified"))
      (node (ref "P2") (pin "6") (pinfunction "6_6") (pintype "unspecified"))
      (node (ref "P2") (pin "8") (pinfunction "8_8") (pintype "unspecified"))
      (node (ref "Q1") (pin "2") (pinfunction "S_2") (pintype "unspecified"))
      (node (ref "R1") (pin "2") (pinfunction "2_2") (pintype "input"))
      (node (ref "R11") (pin "2") (pinfunction "2_2") (pintype "input"))
      (node (ref "R14") (pin "2") (pinfunction "2_2") (pintype "input"))
      (node (ref "R15") (pin "2") (pinfunction "2_2") (pintype "input"))
      (node (ref "R16") (pin "2") (pinfunction "2_2") (pintype "input"))
      (node (ref "R3") (pin "2") (pinfunction "2_2") (pintype "input"))
      (node (ref "R43") (pin "2") (pinfunction "2_2") (pintype "input"))
      (node (ref "R44") (pin "2") (pinfunction "2_2") (pintype "input"))
      (node (ref "R45") (pin "2") (pinfunction "2_2") (pintype "input"))
      (node (ref "R46") (pin "2") (pinfunction "2_2") (pintype "input"))
      (node (ref "R47") (pin "2") (pinfunction "2_2") (pintype "input"))
      (node (ref "R48") (pin "2") (pinfunction "2_2") (pintype "input"))
      (node (ref "R49") (pin "2") (pinfunction "2_2") (pintype "input"))
      (node (ref "R5") (pin "2") (pinfunction "2_2") (pintype "input"))
      (node (ref "R50") (pin "2") (pinfunction "2_2") (pintype "input"))
      (node (ref "R9") (pin "2") (pinfunction "2_2") (pintype "input"))
      (node (ref "U1") (pin "12") (pinfunction "VSSA_12") (pintype "unspecified"))
      (node (ref "U1") (pin "18") (pinfunction "VSS_18") (pintype "unspecified"))
      (node (ref "U1") (pin "2") (pinfunction "PC13/TRC_AF1_2") (pintype "unspecified"))
      (node (ref "U1") (pin "60") (pinfunction "BOOT0_60") (pintype "unspecified"))
      (node (ref "U1") (pin "63") (pinfunction "VSS_63") (pintype "unspecified"))
      (node (ref "U2") (pin "4") (pinfunction "GND_4") (pintype "unspecified"))
      (node (ref "U2") (pin "5") (pinfunction "DIR_5") (pintype "unspecified"))
      (node (ref "U3") (pin "4") (pinfunction "GND_4") (pintype "unspecified"))
      (node (ref "U3") (pin "5") (pinfunction "DIR_5") (pintype "unspecified"))
      (node (ref "U4") (pin "4") (pinfunction "GND_4") (pintype "unspecified"))
      (node (ref "U5") (pin "2") (pinfunction "A1_2") (pintype "unspecified"))
      (node (ref "U5") (pin "4") (pinfunction "GND_4") (pintype "unspecified"))
      (node (ref "U5") (pin "7") (pinfunction "B1_7") (pintype "unspecified"))
      (node (ref "U6") (pin "2") (pinfunction "A1_2") (pintype "unspecified"))
      (node (ref "U6") (pin "4") (pinfunction "GND_4") (pintype "unspecified"))
      (node (ref "U6") (pin "7") (pinfunction "B1_7") (pintype "unspecified"))
      (node (ref "U7") (pin "4") (pinfunction "GND_4") (pintype "unspecified"))
      (node (ref "U8") (pin "4") (pinfunction "GND_4") (pintype "unspecified"))
      (node (ref "U8") (pin "5") (pinfunction "DIR_5") (pintype "unspecified"))
      (node (ref "U9") (pin "4") (pinfunction "V-_4") (pintype "unspecified"))
      (node (ref "X1") (pin "2") (pinfunction "GND_2") (pintype "input"))
      (node (ref "X1") (pin "4") (pinfunction "GND_4") (pintype "input"))
    )
    (net (code "47") (name "Net-(D1-A-Pad3)") (class "Default")
      (node (ref "D1") (pin "3") (pinfunction "A_3") (pintype "unspecified"))
      (node (ref "R7") (pin "1") (pinfunction "1_1") (pintype "input"))
    )
    (net (code "48") (name "Net-(D1-A-Pad4)") (class "Default")
      (node (ref "D1") (pin "4") (pinfunction "A_4") (pintype "unspecified"))
      (node (ref "R6") (pin "1") (pinfunction "1_1") (pintype "input"))
    )
    (net (code "49") (name "Net-(D2-A)") (class "Default")
      (node (ref "D2") (pin "2") (pinfunction "A_2") (pintype "unspecified"))
      (node (ref "U9") (pin "1") (pinfunction "OUTA_1") (pintype "output"))
    )
    (net (code "50") (name "Net-(D2-K)") (class "Default")
      (node (ref "D2") (pin "1") (pinfunction "K_1") (pintype "unspecified"))
      (node (ref "R12") (pin "2") (pinfunction "2_2") (pintype "input"))
    )
    (net (code "51") (name "Net-(D3-A1)") (class "Default")
      (node (ref "D3") (pin "1") (pinfunction "A1_1") (pintype "unspecified"))
      (node (ref "Q2") (pin "3") (pinfunction "G2_3") (pintype "unspecified"))
      (node (ref "R18") (pin "2") (pinfunction "2_2") (pintype "input"))
    )
    (net (code "52") (name "Net-(D3-A2)") (class "Default")
      (node (ref "D3") (pin "2") (pinfunction "A2_2") (pintype "unspecified"))
      (node (ref "Q2") (pin "1") (pinfunction "G1_1") (pintype "unspecified"))
      (node (ref "R21") (pin "1") (pinfunction "1_1") (pintype "input"))
    )
    (net (code "53") (name "Net-(Q1-D)") (class "Default")
      (node (ref "Q1") (pin "3") (pinfunction "D_3") (pintype "unspecified"))
      (node (ref "R20") (pin "1") (pinfunction "1_1") (pintype "input"))
    )
    (net (code "54") (name "Net-(Q2-D1)") (class "Default")
      (node (ref "Q2") (pin "4") (pinfunction "D2_4") (pintype "unspecified"))
      (node (ref "Q2") (pin "6") (pinfunction "D1_6") (pintype "unspecified"))
    )
    (net (code "55") (name "Net-(U1-PH0{slash}OSC_IN)") (class "Default")
      (node (ref "C5") (pin "1") (pinfunction "1_1") (pintype "input"))
      (node (ref "U1") (pin "5") (pinfunction "PH0/OSC_IN_5") (pintype "unspecified"))
      (node (ref "X1") (pin "1") (pinfunction "1_1") (pintype "input"))
    )
    (net (code "56") (name "Net-(U1-PH1{slash}OSC_OUT)") (class "Default")
      (node (ref "C6") (pin "2") (pinfunction "2_2") (pintype "input"))
      (node (ref "U1") (pin "6") (pinfunction "PH1/OSC_OUT_6") (pintype "unspecified"))
      (node (ref "X1") (pin "3") (pinfunction "3_3") (pintype "input"))
    )
    (net (code "57") (name "Net-(U1-VCAP_1)") (class "Default")
      (node (ref "C8") (pin "2") (pinfunction "2_2") (pintype "input"))
      (node (ref "U1") (pin "31") (pinfunction "VCAP_1_31") (pintype "unspecified"))
    )
    (net (code "58") (name "Net-(U1-VCAP_2)") (class "Default")
      (node (ref "C16") (pin "2") (pinfunction "2_2") (pintype "input"))
      (node (ref "U1") (pin "47") (pinfunction "VCAP_2_47") (pintype "unspecified"))
    )
    (net (code "59") (name "Net-(U2-B1)") (class "Default")
      (node (ref "R30") (pin "1") (pinfunction "1_1") (pintype "input"))
      (node (ref "U2") (pin "7") (pinfunction "B1_7") (pintype "unspecified"))
    )
    (net (code "60") (name "Net-(U2-B2)") (class "Default")
      (node (ref "R31") (pin "1") (pinfunction "1_1") (pintype "input"))
      (node (ref "U2") (pin "6") (pinfunction "B2_6") (pintype "unspecified"))
    )
    (net (code "61") (name "Net-(U3-B1)") (class "Default")
      (node (ref "R32") (pin "1") (pinfunction "1_1") (pintype "input"))
      (node (ref "U3") (pin "7") (pinfunction "B1_7") (pintype "unspecified"))
    )
    (net (code "62") (name "Net-(U3-B2)") (class "Default")
      (node (ref "R33") (pin "1") (pinfunction "1_1") (pintype "input"))
      (node (ref "U3") (pin "6") (pinfunction "B2_6") (pintype "unspecified"))
    )
    (net (code "63") (name "Net-(U4-A1)") (class "Default")
      (node (ref "R24") (pin "2") (pinfunction "2_2") (pintype "input"))
      (node (ref "U4") (pin "2") (pinfunction "A1_2") (pintype "unspecified"))
    )
    (net (code "64") (name "Net-(U4-A2)") (class "Default")
      (node (ref "R25") (pin "2") (pinfunction "2_2") (pintype "input"))
      (node (ref "U4") (pin "3") (pinfunction "A2_3") (pintype "unspecified"))
    )
    (net (code "65") (name "Net-(U4-B1)") (class "Default")
      (node (ref "R34") (pin "1") (pinfunction "1_1") (pintype "input"))
      (node (ref "U4") (pin "7") (pinfunction "B1_7") (pintype "unspecified"))
    )
    (net (code "66") (name "Net-(U4-B2)") (class "Default")
      (node (ref "R35") (pin "1") (pinfunction "1_1") (pintype "input"))
      (node (ref "U4") (pin "6") (pinfunction "B2_6") (pintype "unspecified"))
    )
    (net (code "67") (name "Net-(U5-A2)") (class "Default")
      (node (ref "R26") (pin "2") (pinfunction "2_2") (pintype "input"))
      (node (ref "U5") (pin "3") (pinfunction "A2_3") (pintype "unspecified"))
    )
    (net (code "68") (name "Net-(U5-B2)") (class "Default")
      (node (ref "R36") (pin "1") (pinfunction "1_1") (pintype "input"))
      (node (ref "U5") (pin "6") (pinfunction "B2_6") (pintype "unspecified"))
    )
    (net (code "69") (name "Net-(U6-A2)") (class "Default")
      (node (ref "R27") (pin "2") (pinfunction "2_2") (pintype "input"))
      (node (ref "U6") (pin "3") (pinfunction "A2_3") (pintype "unspecified"))
    )
    (net (code "70") (name "Net-(U6-B2)") (class "Default")
      (node (ref "R37") (pin "1") (pinfunction "1_1") (pintype "input"))
      (node (ref "U6") (pin "6") (pinfunction "B2_6") (pintype "unspecified"))
    )
    (net (code "71") (name "Net-(U7-A1)") (class "Default")
      (node (ref "R28") (pin "2") (pinfunction "2_2") (pintype "input"))
      (node (ref "U7") (pin "2") (pinfunction "A1_2") (pintype "unspecified"))
    )
    (net (code "72") (name "Net-(U7-A2)") (class "Default")
      (node (ref "R29") (pin "2") (pinfunction "2_2") (pintype "input"))
      (node (ref "U7") (pin "3") (pinfunction "A2_3") (pintype "unspecified"))
    )
    (net (code "73") (name "Net-(U7-B1)") (class "Default")
      (node (ref "R38") (pin "1") (pinfunction "1_1") (pintype "input"))
      (node (ref "U7") (pin "7") (pinfunction "B1_7") (pintype "unspecified"))
    )
    (net (code "74") (name "Net-(U7-B2)") (class "Default")
      (node (ref "R39") (pin "1") (pinfunction "1_1") (pintype "input"))
      (node (ref "U7") (pin "6") (pinfunction "B2_6") (pintype "unspecified"))
    )
    (net (code "75") (name "Net-(U8-B1)") (class "Default")
      (node (ref "R40") (pin "1") (pinfunction "1_1") (pintype "input"))
      (node (ref "U8") (pin "7") (pinfunction "B1_7") (pintype "unspecified"))
    )
    (net (code "76") (name "Net-(U8-B2)") (class "Default")
      (node (ref "R41") (pin "1") (pinfunction "1_1") (pintype "input"))
      (node (ref "U8") (pin "6") (pinfunction "B2_6") (pintype "unspecified"))
    )
    (net (code "77") (name "Net-(U9A--INA)") (class "Default")
      (node (ref "R4") (pin "2") (pinfunction "2_2") (pintype "input"))
      (node (ref "R5") (pin "1") (pinfunction "1_1") (pintype "input"))
      (node (ref "U9") (pin "2") (pinfunction "-INA_2") (pintype "unspecified"))
    )
    (net (code "78") (name "Net-(U9B-+INB)") (class "Default")
      (node (ref "R17") (pin "1") (pinfunction "1_1") (pintype "input"))
      (node (ref "U9") (pin "5") (pinfunction "+INB_5") (pintype "unspecified"))
    )
    (net (code "79") (name "VIO") (class "Default")
      (node (ref "C21") (pin "2") (pinfunction "2_2") (pintype "input"))
      (node (ref "C22") (pin "2") (pinfunction "2_2") (pintype "input"))
      (node (ref "C23") (pin "2") (pinfunction "2_2") (pintype "input"))
      (node (ref "C24") (pin "2") (pinfunction "2_2") (pintype "input"))
      (node (ref "C9") (pin "2") (pinfunction "2_2") (pintype "input"))
      (node (ref "R12") (pin "1") (pinfunction "1_1") (pintype "input"))
      (node (ref "R15") (pin "1") (pinfunction "1_1") (pintype "input"))
      (node (ref "R19") (pin "1") (pinfunction "1_1") (pintype "input"))
      (node (ref "R4") (pin "1") (pinfunction "1_1") (pintype "input"))
      (node (ref "R42") (pin "2") (pinfunction "2_2") (pintype "input"))
      (node (ref "U2") (pin "8") (pinfunction "VCCB_8") (pintype "unspecified"))
      (node (ref "U3") (pin "8") (pinfunction "VCCB_8") (pintype "unspecified"))
      (node (ref "U4") (pin "8") (pinfunction "VCCB_8") (pintype "unspecified"))
      (node (ref "U5") (pin "8") (pinfunction "VCCB_8") (pintype "unspecified"))
      (node (ref "U6") (pin "8") (pinfunction "VCCB_8") (pintype "unspecified"))
      (node (ref "U7") (pin "8") (pinfunction "VCCB_8") (pintype "unspecified"))
      (node (ref "U8") (pin "8") (pinfunction "VCCB_8") (pintype "unspecified"))
    )
    (net (code "80") (name "unconnected-(P1-Pad10)") (class "Default")
      (node (ref "P1") (pin "10") (pinfunction "10_10") (pintype "unspecified+no_connect"))
    )
    (net (code "81") (name "unconnected-(P1-Pad12)") (class "Default")
      (node (ref "P1") (pin "12") (pinfunction "12_12") (pintype "unspecified+no_connect"))
    )
    (net (code "82") (name "unconnected-(P2-Pad2)") (class "Default")
      (node (ref "P2") (pin "2") (pinfunction "2_2") (pintype "unspecified+no_connect"))
    )
    (net (code "83") (name "unconnected-(P3-Pad1)") (class "Default")
      (node (ref "P3") (pin "1") (pinfunction "1_1") (pintype "unspecified"))
    )
    (net (code "84") (name "unconnected-(P3-Pad2)") (class "Default")
      (node (ref "P3") (pin "2") (pinfunction "2_2") (pintype "unspecified"))
    )
    (net (code "85") (name "unconnected-(P3-Pad3)") (class "Default")
      (node (ref "P3") (pin "3") (pinfunction "3_3") (pintype "unspecified"))
    )
    (net (code "86") (name "unconnected-(P3-Pad4)") (class "Default")
      (node (ref "P3") (pin "4") (pinfunction "4_4") (pintype "unspecified"))
    )
    (net (code "87") (name "unconnected-(P3-Pad5)") (class "Default")
      (node (ref "P3") (pin "5") (pinfunction "5_5") (pintype "unspecified"))
    )
    (net (code "88") (name "unconnected-(U1-PA9-Pad42)") (class "Default")
      (node (ref "U1") (pin "42") (pinfunction "PA9_42") (pintype "unspecified+no_connect"))
    )
    (net (code "89") (name "unconnected-(U1-PA15-Pad50)") (class "Default")
      (node (ref "U1") (pin "50") (pinfunction "PA15_50") (pintype "unspecified+no_connect"))
    )
    (net (code "90") (name "unconnected-(U1-PB3-Pad55)") (class "Default")
      (node (ref "U1") (pin "55") (pinfunction "PB3_55") (pintype "unspecified+no_connect"))
    )
    (net (code "91") (name "unconnected-(U1-PB4-Pad56)") (class "Default")
      (node (ref "U1") (pin "56") (pinfunction "PB4_56") (pintype "unspecified+no_connect"))
    )
    (net (code "92") (name "unconnected-(U1-PB5-Pad57)") (class "Default")
      (node (ref "U1") (pin "57") (pinfunction "PB5_57") (pintype "unspecified+no_connect"))
    )
    (net (code "93") (name "unconnected-(U1-PB6-Pad58)") (class "Default")
      (node (ref "U1") (pin "58") (pinfunction "PB6_58") (pintype "unspecified+no_connect"))
    )
    (net (code "94") (name "unconnected-(U1-PB9-Pad62)") (class "Default")
      (node (ref "U1") (pin "62") (pinfunction "PB9_62") (pintype "unspecified+no_connect"))
    )
    (net (code "95") (name "unconnected-(U1-PC4-Pad24)") (class "Default")
      (node (ref "U1") (pin "24") (pinfunction "PC4_24") (pintype "unspecified+no_connect"))
    )
    (net (code "96") (name "unconnected-(U1-PC11-Pad52)") (class "Default")
      (node (ref "U1") (pin "52") (pinfunction "PC11_52") (pintype "unspecified+no_connect"))
    )
    (net (code "97") (name "unconnected-(U1-PC14{slash}OSC32_IN-Pad3)") (class "Default")
      (node (ref "U1") (pin "3") (pinfunction "PC14/OSC32_IN_3") (pintype "unspecified+no_connect"))
    )
    (net (code "98") (name "unconnected-(U1-PC15{slash}OSC32_OUT-Pad4)") (class "Default")
      (node (ref "U1") (pin "4") (pinfunction "PC15/OSC32_OUT_4") (pintype "unspecified+no_connect"))
    )
    (net (code "99") (name "unconnected-(U1-PD2-Pad54)") (class "Default")
      (node (ref "U1") (pin "54") (pinfunction "PD2_54") (pintype "unspecified+no_connect"))
    )
  )
)
